# 3_-MCU.net
KiCad netlist of a schematic drawn in Altium Designer
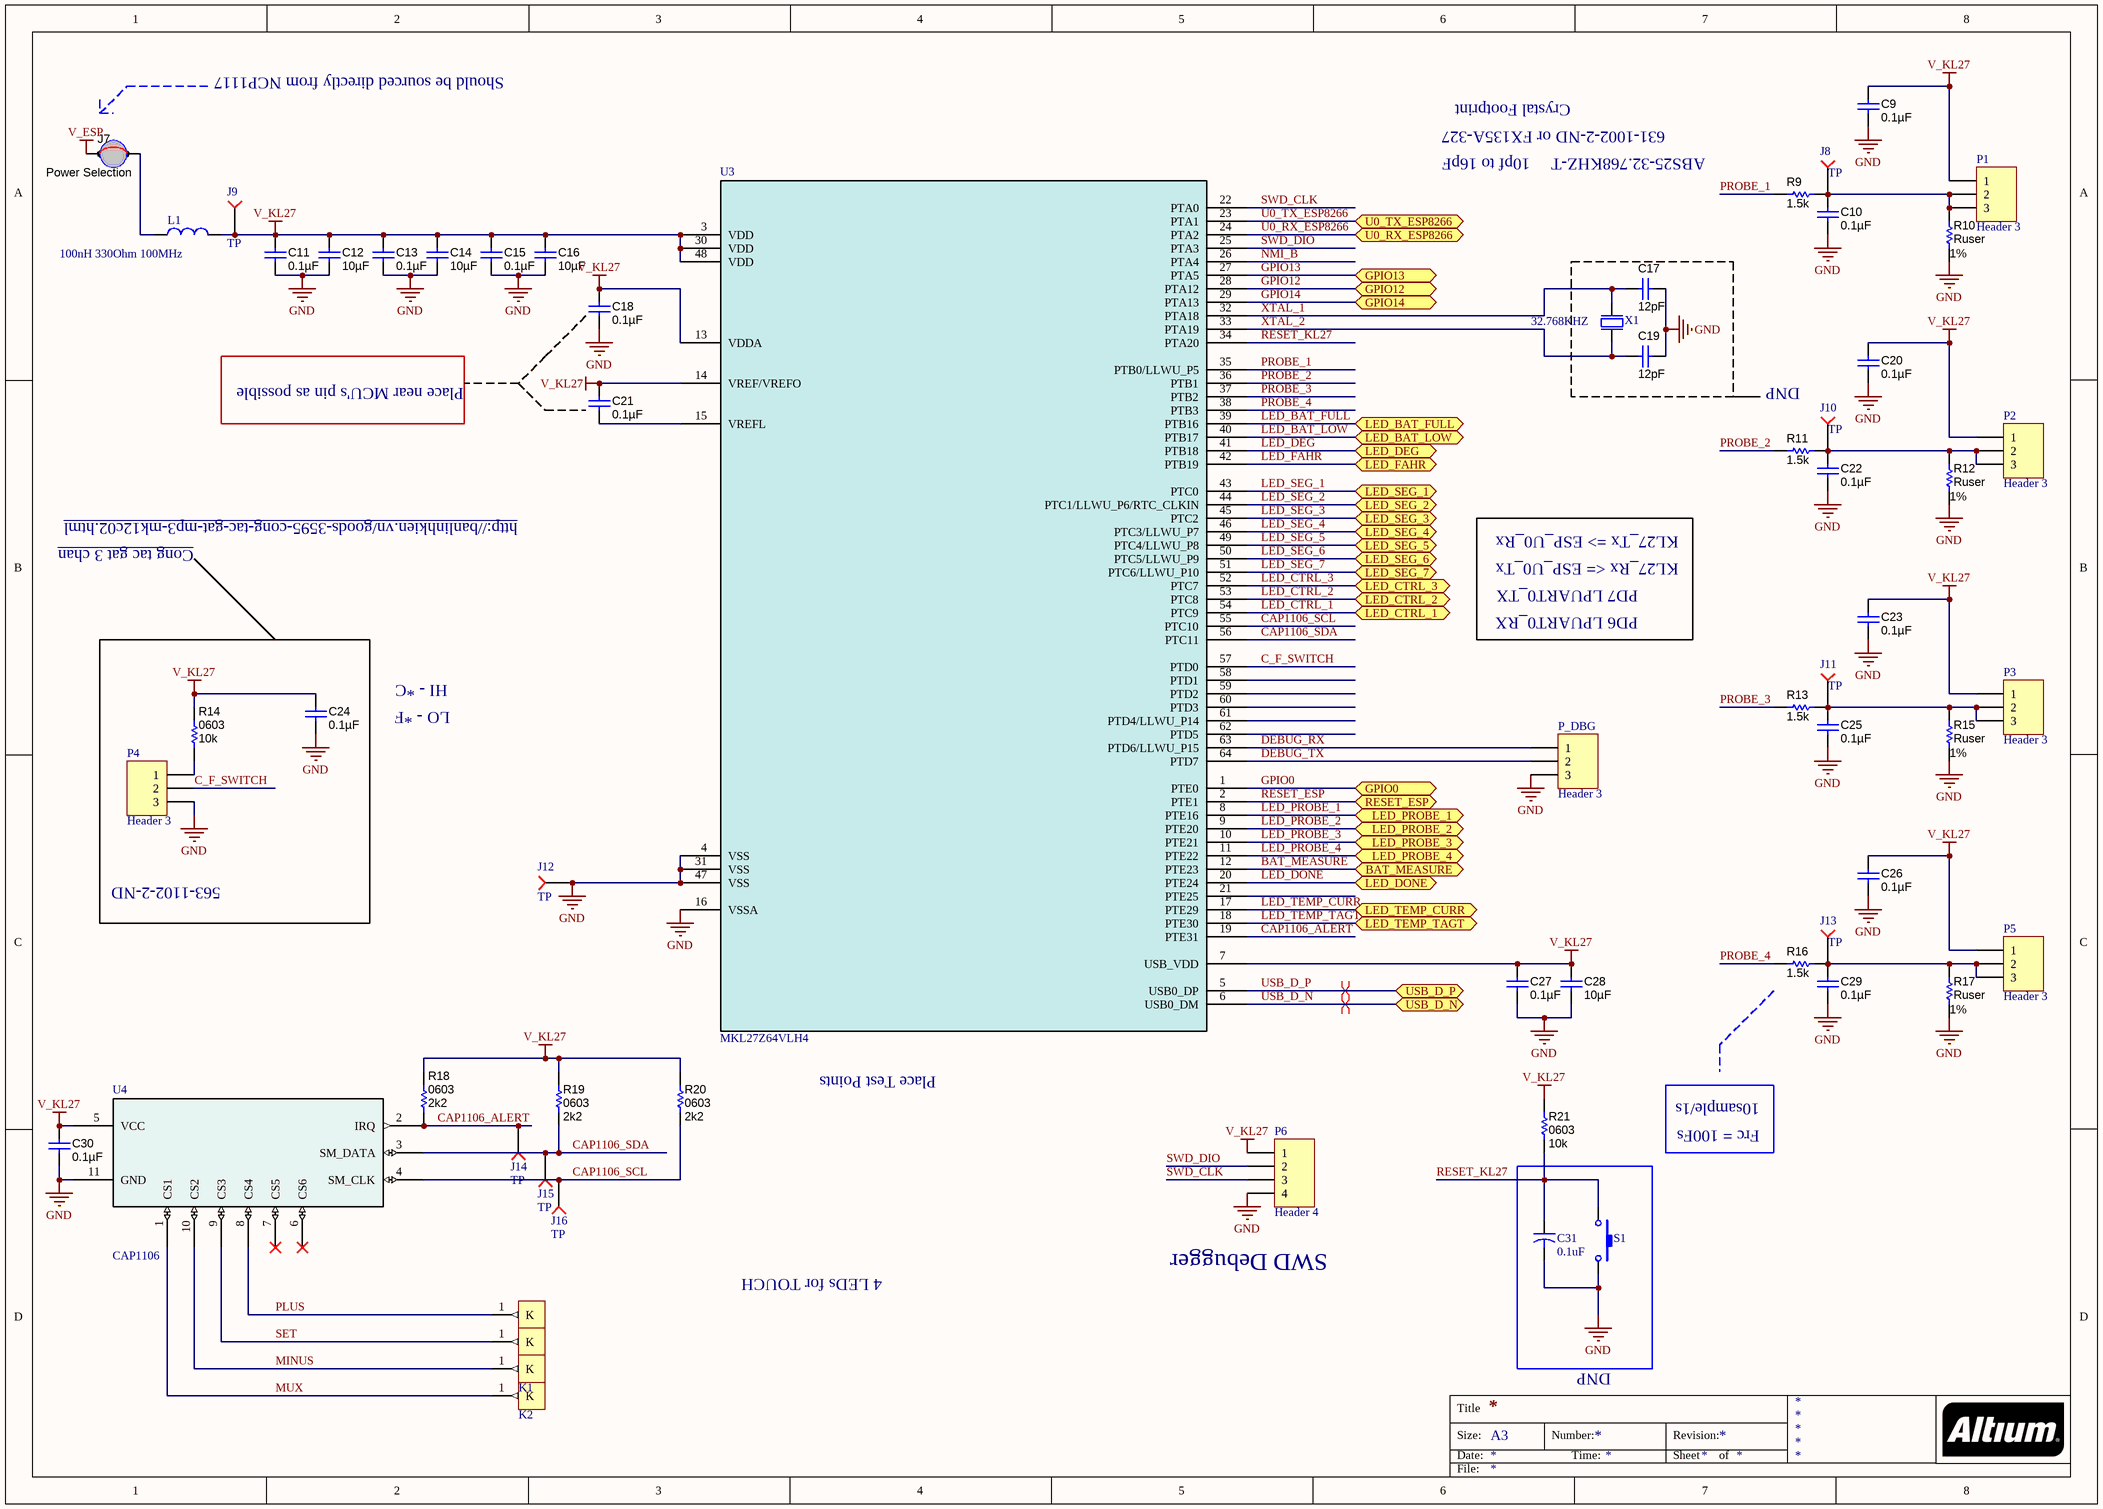
[diagram p0: [3]-MCU.SchDoc]

(export (version "E")
  (design (tool "Eeschema 10.0.6"))
  (components
    (comp (ref "C9")
      (value "0603YC104JAT2A")
      (footprint "0603")
      (description "CAP, CERM, 0.1uF, 16V, +/-5%, X7R, 0603")
      (fields
        (field (name "MANUFACTURER") "AVX")
        (field (name "VALUEDISPLAYED") "0.1µF")
        (field (name "PUBLISHER") "Texas Instruments")
      )
      (libsource (lib "tuongpv2") (part "Cap_0603"))
    )
    (comp (ref "C10")
      (value "0603YC104JAT2A")
      (footprint "0603")
      (description "CAP, CERM, 0.1uF, 16V, +/-5%, X7R, 0603")
      (fields
        (field (name "MANUFACTURER") "AVX")
        (field (name "VALUEDISPLAYED") "0.1µF")
        (field (name "PUBLISHER") "Texas Instruments")
      )
      (libsource (lib "tuongpv2") (part "Cap_0603"))
    )
    (comp (ref "C11")
      (value "0603YC104JAT2A")
      (footprint "0603")
      (description "CAP, CERM, 0.1uF, 16V, +/-5%, X7R, 0603")
      (fields
        (field (name "MANUFACTURER") "AVX")
        (field (name "VALUEDISPLAYED") "0.1µF")
        (field (name "PUBLISHER") "Texas Instruments")
      )
      (libsource (lib "tuongpv2") (part "Cap_0603"))
    )
    (comp (ref "C12")
      (value "0603YC104JAT2A")
      (footprint "0603")
      (description "CAP, CERM, 0.1uF, 16V, +/-5%, X7R, 0603")
      (fields
        (field (name "MANUFACTURER") "AVX")
        (field (name "VALUEDISPLAYED") "10µF")
        (field (name "PUBLISHER") "Texas Instruments")
      )
      (libsource (lib "tuongpv2") (part "Cap_0603"))
    )
    (comp (ref "C13")
      (value "0603YC104JAT2A")
      (footprint "0603")
      (description "CAP, CERM, 0.1uF, 16V, +/-5%, X7R, 0603")
      (fields
        (field (name "MANUFACTURER") "AVX")
        (field (name "VALUEDISPLAYED") "0.1µF")
        (field (name "PUBLISHER") "Texas Instruments")
      )
      (libsource (lib "tuongpv2") (part "Cap_0603"))
    )
    (comp (ref "C14")
      (value "0603YC104JAT2A")
      (footprint "0603")
      (description "CAP, CERM, 0.1uF, 16V, +/-5%, X7R, 0603")
      (fields
        (field (name "MANUFACTURER") "AVX")
        (field (name "VALUEDISPLAYED") "10µF")
        (field (name "PUBLISHER") "Texas Instruments")
      )
      (libsource (lib "tuongpv2") (part "Cap_0603"))
    )
    (comp (ref "C15")
      (value "0603YC104JAT2A")
      (footprint "0603")
      (description "CAP, CERM, 0.1uF, 16V, +/-5%, X7R, 0603")
      (fields
        (field (name "MANUFACTURER") "AVX")
        (field (name "VALUEDISPLAYED") "0.1µF")
        (field (name "PUBLISHER") "Texas Instruments")
      )
      (libsource (lib "tuongpv2") (part "Cap_0603"))
    )
    (comp (ref "C16")
      (value "0603YC104JAT2A")
      (footprint "0603")
      (description "CAP, CERM, 0.1uF, 16V, +/-5%, X7R, 0603")
      (fields
        (field (name "MANUFACTURER") "AVX")
        (field (name "VALUEDISPLAYED") "10µF")
        (field (name "PUBLISHER") "Texas Instruments")
      )
      (libsource (lib "tuongpv2") (part "Cap_0603"))
    )
    (comp (ref "C17")
      (value "0603YC104JAT2A")
      (footprint "0603")
      (description "CAP, CERM, 0.1uF, 16V, +/-5%, X7R, 0603")
      (fields
        (field (name "MANUFACTURER") "AVX")
        (field (name "VALUEDISPLAYED") "12pF")
        (field (name "PUBLISHER") "Texas Instruments")
      )
      (libsource (lib "tuongpv2") (part "Cap_0603"))
    )
    (comp (ref "C18")
      (value "0603YC104JAT2A")
      (footprint "0603")
      (description "CAP, CERM, 0.1uF, 16V, +/-5%, X7R, 0603")
      (fields
        (field (name "MANUFACTURER") "AVX")
        (field (name "VALUEDISPLAYED") "0.1µF")
        (field (name "PUBLISHER") "Texas Instruments")
      )
      (libsource (lib "tuongpv2") (part "Cap_0603"))
    )
    (comp (ref "C19")
      (value "0603YC104JAT2A")
      (footprint "0603")
      (description "CAP, CERM, 0.1uF, 16V, +/-5%, X7R, 0603")
      (fields
        (field (name "MANUFACTURER") "AVX")
        (field (name "VALUEDISPLAYED") "12pF")
        (field (name "PUBLISHER") "Texas Instruments")
      )
      (libsource (lib "tuongpv2") (part "Cap_0603"))
    )
    (comp (ref "C20")
      (value "0603YC104JAT2A")
      (footprint "0603")
      (description "CAP, CERM, 0.1uF, 16V, +/-5%, X7R, 0603")
      (fields
        (field (name "MANUFACTURER") "AVX")
        (field (name "VALUEDISPLAYED") "0.1µF")
        (field (name "PUBLISHER") "Texas Instruments")
      )
      (libsource (lib "tuongpv2") (part "Cap_0603"))
    )
    (comp (ref "C21")
      (value "0603YC104JAT2A")
      (footprint "0603")
      (description "CAP, CERM, 0.1uF, 16V, +/-5%, X7R, 0603")
      (fields
        (field (name "MANUFACTURER") "AVX")
        (field (name "VALUEDISPLAYED") "0.1µF")
        (field (name "PUBLISHER") "Texas Instruments")
      )
      (libsource (lib "tuongpv2") (part "Cap_0603"))
    )
    (comp (ref "C22")
      (value "0603YC104JAT2A")
      (footprint "0603")
      (description "CAP, CERM, 0.1uF, 16V, +/-5%, X7R, 0603")
      (fields
        (field (name "MANUFACTURER") "AVX")
        (field (name "VALUEDISPLAYED") "0.1µF")
        (field (name "PUBLISHER") "Texas Instruments")
      )
      (libsource (lib "tuongpv2") (part "Cap_0603"))
    )
    (comp (ref "C23")
      (value "0603YC104JAT2A")
      (footprint "0603")
      (description "CAP, CERM, 0.1uF, 16V, +/-5%, X7R, 0603")
      (fields
        (field (name "MANUFACTURER") "AVX")
        (field (name "VALUEDISPLAYED") "0.1µF")
        (field (name "PUBLISHER") "Texas Instruments")
      )
      (libsource (lib "tuongpv2") (part "Cap_0603"))
    )
    (comp (ref "C24")
      (value "0603YC104JAT2A")
      (footprint "0603")
      (description "CAP, CERM, 0.1uF, 16V, +/-5%, X7R, 0603")
      (fields
        (field (name "MANUFACTURER") "AVX")
        (field (name "VALUEDISPLAYED") "0.1µF")
        (field (name "PUBLISHER") "Texas Instruments")
      )
      (libsource (lib "tuongpv2") (part "Cap_0603"))
    )
    (comp (ref "C25")
      (value "0603YC104JAT2A")
      (footprint "0603")
      (description "CAP, CERM, 0.1uF, 16V, +/-5%, X7R, 0603")
      (fields
        (field (name "MANUFACTURER") "AVX")
        (field (name "VALUEDISPLAYED") "0.1µF")
        (field (name "PUBLISHER") "Texas Instruments")
      )
      (libsource (lib "tuongpv2") (part "Cap_0603"))
    )
    (comp (ref "C26")
      (value "0603YC104JAT2A")
      (footprint "0603")
      (description "CAP, CERM, 0.1uF, 16V, +/-5%, X7R, 0603")
      (fields
        (field (name "MANUFACTURER") "AVX")
        (field (name "VALUEDISPLAYED") "0.1µF")
        (field (name "PUBLISHER") "Texas Instruments")
      )
      (libsource (lib "tuongpv2") (part "Cap_0603"))
    )
    (comp (ref "C27")
      (value "0603YC104JAT2A")
      (footprint "0603")
      (description "CAP, CERM, 0.1uF, 16V, +/-5%, X7R, 0603")
      (fields
        (field (name "MANUFACTURER") "AVX")
        (field (name "VALUEDISPLAYED") "0.1µF")
        (field (name "PUBLISHER") "Texas Instruments")
      )
      (libsource (lib "tuongpv2") (part "Cap_0603"))
    )
    (comp (ref "C28")
      (value "0603YC104JAT2A")
      (footprint "0603")
      (description "CAP, CERM, 0.1uF, 16V, +/-5%, X7R, 0603")
      (fields
        (field (name "MANUFACTURER") "AVX")
        (field (name "VALUEDISPLAYED") "10µF")
        (field (name "PUBLISHER") "Texas Instruments")
      )
      (libsource (lib "tuongpv2") (part "Cap_0603"))
    )
    (comp (ref "C29")
      (value "0603YC104JAT2A")
      (footprint "0603")
      (description "CAP, CERM, 0.1uF, 16V, +/-5%, X7R, 0603")
      (fields
        (field (name "MANUFACTURER") "AVX")
        (field (name "VALUEDISPLAYED") "0.1µF")
        (field (name "PUBLISHER") "Texas Instruments")
      )
      (libsource (lib "tuongpv2") (part "Cap_0603"))
    )
    (comp (ref "C30")
      (value "0603YC104JAT2A")
      (footprint "0603")
      (description "CAP, CERM, 0.1uF, 16V, +/-5%, X7R, 0603")
      (fields
        (field (name "MANUFACTURER") "AVX")
        (field (name "VALUEDISPLAYED") "0.1µF")
        (field (name "PUBLISHER") "Texas Instruments")
      )
      (libsource (lib "tuongpv2") (part "Cap_0603"))
    )
    (comp (ref "C31")
      (value "0.1uF")
      (footprint "0603")
      (description "Ceramic")
      (fields (field (name "PUBLISHER") "Altium Limited"))
      (libsource (lib "Capacitor") (part "Cap 0805"))
    )
    (comp (ref "J7")
      (value "Power Selection")
      (footprint "HDR1X2")
      (description "Jumper Wire, 200mil spacing, Red, pkg of 200")
      (fields
        (field (name "PARTNUMBER") "923345-02-C")
        (field (name "MANUFACTURER") "3M")
        (field (name "SYMBOLCREATOR") "a0412235")
        (field (name "PUBLISHER") "Texas Instruments")
      )
      (libsource (lib "Connectors") (part "923345-02-C"))
    )
    (comp (ref "J8")
      (value "TP")
      (footprint "TP")
      (description "Test point (true)")
      (libsource (lib "Cty1") (part "TP"))
    )
    (comp (ref "J9")
      (value "TP")
      (footprint "TP")
      (description "Test point (true)")
      (libsource (lib "Cty1") (part "TP"))
    )
    (comp (ref "J10")
      (value "TP")
      (footprint "TP")
      (description "Test point (true)")
      (libsource (lib "Cty1") (part "TP"))
    )
    (comp (ref "J11")
      (value "TP")
      (footprint "TP")
      (description "Test point (true)")
      (libsource (lib "Cty1") (part "TP"))
    )
    (comp (ref "J12")
      (value "TP")
      (footprint "TP")
      (description "Test point (true)")
      (libsource (lib "Cty1") (part "TP"))
    )
    (comp (ref "J13")
      (value "TP")
      (footprint "TP")
      (description "Test point (true)")
      (libsource (lib "Cty1") (part "TP"))
    )
    (comp (ref "J14")
      (value "TP")
      (footprint "TP")
      (description "Test point (true)")
      (libsource (lib "Cty1") (part "TP"))
    )
    (comp (ref "J15")
      (value "TP")
      (footprint "TP")
      (description "Test point (true)")
      (libsource (lib "Cty1") (part "TP"))
    )
    (comp (ref "J16")
      (value "TP")
      (footprint "TP")
      (description "Test point (true)")
      (libsource (lib "Cty1") (part "TP"))
    )
    (comp (ref "K1")
      (value "Single_Key")
      (footprint "PAD_FINGETIP")
      (description "Single Key Touch")
      (fields (field (name "CREATED BY") "TuongPV"))
      (libsource (lib "TouchLib") (part "Single_Key"))
    )
    (comp (ref "K2")
      (value "Single_Key")
      (footprint "PAD_FINGETIP")
      (description "Single Key Touch")
      (fields (field (name "CREATED BY") "TuongPV"))
      (libsource (lib "TouchLib") (part "Single_Key"))
    )
    (comp (ref "K3")
      (value "Single_Key")
      (footprint "PAD_FINGETIP")
      (description "Single Key Touch")
      (fields (field (name "CREATED BY") "TuongPV"))
      (libsource (lib "TouchLib") (part "Single_Key"))
    )
    (comp (ref "K4")
      (value "Single_Key")
      (footprint "PAD_FINGETIP")
      (description "Single Key Touch")
      (fields (field (name "CREATED BY") "TuongPV"))
      (libsource (lib "TouchLib") (part "Single_Key"))
    )
    (comp (ref "L1")
      (value "100nH 330Ohm 100MHz")
      (footprint "0805")
      (description "Inductor")
      (libsource (lib "TuongLib") (part "L1"))
    )
    (comp (ref "P1")
      (value "Header 3")
      (footprint "JACK_MONO")
      (description "Header, 3-Pin")
      (fields (field (name "PUBLISHER") "Altium Limited"))
      (libsource (lib "Connecter") (part "Header 3"))
    )
    (comp (ref "P2")
      (value "Header 3")
      (footprint "JACK_MONO")
      (description "Header, 3-Pin")
      (fields (field (name "PUBLISHER") "Altium Limited"))
      (libsource (lib "Connecter") (part "Header 3"))
    )
    (comp (ref "P3")
      (value "Header 3")
      (footprint "JACK_MONO")
      (description "Header, 3-Pin")
      (fields (field (name "PUBLISHER") "Altium Limited"))
      (libsource (lib "Connecter") (part "Header 3"))
    )
    (comp (ref "P4")
      (value "Header 3")
      (footprint "SW_Slide")
      (description "Header, 3-Pin")
      (fields (field (name "PUBLISHER") "Altium Limited"))
      (libsource (lib "") (part "Header 3_1"))
    )
    (comp (ref "P5")
      (value "Header 3")
      (footprint "JACK_MONO")
      (description "Header, 3-Pin")
      (fields (field (name "PUBLISHER") "Altium Limited"))
      (libsource (lib "Connecter") (part "Header 3"))
    )
    (comp (ref "P6")
      (value "Header 4")
      (footprint "hdR1x4")
      (description "Header, 4-Pin")
      (fields (field (name "PUBLISHER") "Altium Limited"))
      (libsource (lib "Connecter") (part "Header 4"))
    )
    (comp (ref "P_DBG")
      (value "Header 3")
      (footprint "HDR1X3")
      (description "Header, 3-Pin")
      (fields (field (name "PUBLISHER") "Altium Limited"))
      (libsource (lib "Connecter") (part "Header 3"))
    )
    (comp (ref "R9")
      (value "1.5k")
      (footprint "0603")
      (description "RES, 1.00k ohm, 1%, 0.1W, 0603")
      (fields
        (field (name "PARTNUMBER") "CRCW06031K00FKEA")
        (field (name "MANUFACTURER") "Vishay-Dale")
        (field (name "PUBLISHER") "Texas Instruments")
      )
      (libsource (lib "tuongpv2") (part "R0603"))
    )
    (comp (ref "R10")
      (value "Ruser")
      (footprint "0603")
      (description "RES, 1.00k ohm, 1%, 0.1W, 0603")
      (fields
        (field (name "PARTNUMBER") "CRCW06031K00FKEA")
        (field (name "MANUFACTURER") "Vishay-Dale")
        (field (name "VALUE1") "1%")
        (field (name "PUBLISHER") "Texas Instruments")
      )
      (libsource (lib "tuongpv2") (part "R0603"))
    )
    (comp (ref "R11")
      (value "1.5k")
      (footprint "0603")
      (description "RES, 1.00k ohm, 1%, 0.1W, 0603")
      (fields
        (field (name "PARTNUMBER") "CRCW06031K00FKEA")
        (field (name "MANUFACTURER") "Vishay-Dale")
        (field (name "PUBLISHER") "Texas Instruments")
      )
      (libsource (lib "tuongpv2") (part "R0603"))
    )
    (comp (ref "R12")
      (value "Ruser")
      (footprint "0603")
      (description "RES, 1.00k ohm, 1%, 0.1W, 0603")
      (fields
        (field (name "PARTNUMBER") "CRCW06031K00FKEA")
        (field (name "MANUFACTURER") "Vishay-Dale")
        (field (name "VALUE1") "1%")
        (field (name "PUBLISHER") "Texas Instruments")
      )
      (libsource (lib "tuongpv2") (part "R0603"))
    )
    (comp (ref "R13")
      (value "1.5k")
      (footprint "0603")
      (description "RES, 1.00k ohm, 1%, 0.1W, 0603")
      (fields
        (field (name "PARTNUMBER") "CRCW06031K00FKEA")
        (field (name "MANUFACTURER") "Vishay-Dale")
        (field (name "PUBLISHER") "Texas Instruments")
      )
      (libsource (lib "tuongpv2") (part "R0603"))
    )
    (comp (ref "R14")
      (value "10k")
      (footprint "0603")
      (description "RES 5%, 0.125W, 0805")
      (fields
        (field (name "PARTNUMBER") "CRCW08051K00JNEA")
        (field (name "MANUFACTURER") "Vishay-Dale")
        (field (name "VALUE1") "0603")
        (field (name "PUBLISHER") "Texas Instruments")
      )
      (libsource (lib "Cty1") (part "R0805_025W"))
    )
    (comp (ref "R15")
      (value "Ruser")
      (footprint "0603")
      (description "RES, 1.00k ohm, 1%, 0.1W, 0603")
      (fields
        (field (name "PARTNUMBER") "CRCW06031K00FKEA")
        (field (name "MANUFACTURER") "Vishay-Dale")
        (field (name "VALUE1") "1%")
        (field (name "PUBLISHER") "Texas Instruments")
      )
      (libsource (lib "tuongpv2") (part "R0603"))
    )
    (comp (ref "R16")
      (value "1.5k")
      (footprint "0603")
      (description "RES, 1.00k ohm, 1%, 0.1W, 0603")
      (fields
        (field (name "PARTNUMBER") "CRCW06031K00FKEA")
        (field (name "MANUFACTURER") "Vishay-Dale")
        (field (name "PUBLISHER") "Texas Instruments")
      )
      (libsource (lib "tuongpv2") (part "R0603"))
    )
    (comp (ref "R17")
      (value "Ruser")
      (footprint "0603")
      (description "RES, 1.00k ohm, 1%, 0.1W, 0603")
      (fields
        (field (name "PARTNUMBER") "CRCW06031K00FKEA")
        (field (name "MANUFACTURER") "Vishay-Dale")
        (field (name "VALUE1") "1%")
        (field (name "PUBLISHER") "Texas Instruments")
      )
      (libsource (lib "tuongpv2") (part "R0603"))
    )
    (comp (ref "R18")
      (value "2k2")
      (footprint "0603")
      (description "RES 5%, 0.125W, 0805")
      (fields
        (field (name "PARTNUMBER") "CRCW08051K00JNEA")
        (field (name "MANUFACTURER") "Vishay-Dale")
        (field (name "VALUE1") "0603")
        (field (name "PUBLISHER") "Texas Instruments")
      )
      (libsource (lib "Cty1") (part "R0805_025W"))
    )
    (comp (ref "R19")
      (value "2k2")
      (footprint "0603")
      (description "RES 5%, 0.125W, 0805")
      (fields
        (field (name "PARTNUMBER") "CRCW08051K00JNEA")
        (field (name "MANUFACTURER") "Vishay-Dale")
        (field (name "VALUE1") "0603")
        (field (name "PUBLISHER") "Texas Instruments")
      )
      (libsource (lib "Cty1") (part "R0805_025W"))
    )
    (comp (ref "R20")
      (value "2k2")
      (footprint "0603")
      (description "RES 5%, 0.125W, 0805")
      (fields
        (field (name "PARTNUMBER") "CRCW08051K00JNEA")
        (field (name "MANUFACTURER") "Vishay-Dale")
        (field (name "VALUE1") "0603")
        (field (name "PUBLISHER") "Texas Instruments")
      )
      (libsource (lib "Cty1") (part "R0805_025W"))
    )
    (comp (ref "R21")
      (value "10k")
      (footprint "0603")
      (description "RES 5%, 0.125W, 0805")
      (fields
        (field (name "PARTNUMBER") "CRCW08051K00JNEA")
        (field (name "MANUFACTURER") "Vishay-Dale")
        (field (name "VALUE1") "0603")
        (field (name "PUBLISHER") "Texas Instruments")
      )
      (libsource (lib "Cty1") (part "R0805_025W"))
    )
    (comp (ref "S1")
      (value "SW-SMD")
      (footprint "SW-SMD")
      (description "Switch")
      (fields (field (name "PUBLISHER") "Altium Limited"))
      (libsource (lib "Cty1") (part "SW-SMD"))
    )
    (comp (ref "U3")
      (value "MKL27Z64VLH4")
      (footprint "98ASS23234W")
      (description "ARM cortex M0+ 64Kb Flash LQFP-64")
      (fields (field (name "MANUFACTURER_PART_NUMBER") "mkl27z64vlh4"))
      (libsource (lib "uC") (part "MKL27Z64VLH4"))
    )
    (comp (ref "U4")
      (value "CAP1106")
      (footprint "TDFN33-10pin")
      (description "6 Channel Capacitive Touch Sensor")
      (fields (field (name "MANUFACTURER") "Microchip"))
      (libsource (lib "SMPS_IC") (part "CAP1106"))
    )
    (comp (ref "X1")
      (value "32.768KHZ")
      (footprint "XTAL_3215")
      (description "XTAL SMD 3215, 32.768kHz, 9pF, ±20ppm")
      (fields
        (field (name "PART NUMBER") "XTAL_FC-135 32.768k")
        (field (name "MANUFACTURER") "Epson Toyocom")
        (field (name "PUBLISHER") "Nordic Semiconductor")
      )
      (libsource (lib "Cty1") (part "XTAL_SMD3215"))
    )
  )
  (nets
    (net (code "1") (name "/BAT_MEASURE") (class "Default")
      (node (ref "U3") (pin "12") (pinfunction "PTE23_12") (pintype "passive"))
    )
    (net (code "2") (name "/CAP1106_ALERT") (class "Default")
      (node (ref "J14") (pin "0") (pinfunction "0_0") (pintype "passive"))
      (node (ref "R18") (pin "2") (pinfunction "2_2") (pintype "passive"))
      (node (ref "U3") (pin "19") (pinfunction "PTE31_19") (pintype "passive"))
      (node (ref "U4") (pin "2") (pinfunction "IRQ_2") (pintype "output"))
    )
    (net (code "3") (name "/CAP1106_SCL") (class "Default")
      (node (ref "J16") (pin "0") (pinfunction "0_0") (pintype "passive"))
      (node (ref "R20") (pin "2") (pinfunction "2_2") (pintype "passive"))
      (node (ref "U3") (pin "55") (pinfunction "PTC10_55") (pintype "passive"))
      (node (ref "U4") (pin "4") (pinfunction "SM_CLK_4") (pintype "bidirectional"))
    )
    (net (code "4") (name "/CAP1106_SDA") (class "Default")
      (node (ref "J15") (pin "0") (pinfunction "0_0") (pintype "passive"))
      (node (ref "R19") (pin "2") (pinfunction "2_2") (pintype "passive"))
      (node (ref "U3") (pin "56") (pinfunction "PTC11_56") (pintype "passive"))
      (node (ref "U4") (pin "3") (pinfunction "SM_DATA_3") (pintype "bidirectional"))
    )
    (net (code "5") (name "/C_F_SWITCH") (class "Default")
      (node (ref "P4") (pin "2") (pinfunction "2_2") (pintype "passive"))
      (node (ref "U3") (pin "57") (pinfunction "PTD0_57") (pintype "passive"))
    )
    (net (code "6") (name "/DEBUG_RX") (class "Default")
      (node (ref "P_DBG") (pin "1") (pinfunction "1_1") (pintype "passive"))
      (node (ref "U3") (pin "63") (pinfunction "PTD6/LLWU_P15_63") (pintype "passive"))
    )
    (net (code "7") (name "/DEBUG_TX") (class "Default")
      (node (ref "P_DBG") (pin "2") (pinfunction "2_2") (pintype "passive"))
      (node (ref "U3") (pin "64") (pinfunction "PTD7_64") (pintype "passive"))
    )
    (net (code "8") (name "/GPIO0") (class "Default")
      (node (ref "U3") (pin "1") (pinfunction "PTE0_1") (pintype "passive"))
    )
    (net (code "9") (name "/GPIO12") (class "Default")
      (node (ref "U3") (pin "28") (pinfunction "PTA12_28") (pintype "passive"))
    )
    (net (code "10") (name "/GPIO13") (class "Default")
      (node (ref "U3") (pin "27") (pinfunction "PTA5_27") (pintype "passive"))
    )
    (net (code "11") (name "/GPIO14") (class "Default")
      (node (ref "U3") (pin "29") (pinfunction "PTA13_29") (pintype "passive"))
    )
    (net (code "12") (name "/LED_BAT_FULL") (class "Default")
      (node (ref "U3") (pin "39") (pinfunction "PTB16_39") (pintype "passive"))
    )
    (net (code "13") (name "/LED_BAT_LOW") (class "Default")
      (node (ref "U3") (pin "40") (pinfunction "PTB17_40") (pintype "passive"))
    )
    (net (code "14") (name "/LED_CTRL_1") (class "Default")
      (node (ref "U3") (pin "54") (pinfunction "PTC9_54") (pintype "passive"))
    )
    (net (code "15") (name "/LED_CTRL_2") (class "Default")
      (node (ref "U3") (pin "53") (pinfunction "PTC8_53") (pintype "passive"))
    )
    (net (code "16") (name "/LED_CTRL_3") (class "Default")
      (node (ref "U3") (pin "52") (pinfunction "PTC7_52") (pintype "passive"))
    )
    (net (code "17") (name "/LED_DEG") (class "Default")
      (node (ref "U3") (pin "41") (pinfunction "PTB18_41") (pintype "passive"))
    )
    (net (code "18") (name "/LED_DONE") (class "Default")
      (node (ref "U3") (pin "20") (pinfunction "PTE24_20") (pintype "passive"))
    )
    (net (code "19") (name "/LED_FAHR") (class "Default")
      (node (ref "U3") (pin "42") (pinfunction "PTB19_42") (pintype "passive"))
    )
    (net (code "20") (name "/LED_PROBE_1") (class "Default")
      (node (ref "U3") (pin "8") (pinfunction "PTE16_8") (pintype "passive"))
    )
    (net (code "21") (name "/LED_PROBE_2") (class "Default")
      (node (ref "U3") (pin "9") (pinfunction "PTE20_9") (pintype "passive"))
    )
    (net (code "22") (name "/LED_PROBE_3") (class "Default")
      (node (ref "U3") (pin "10") (pinfunction "PTE21_10") (pintype "passive"))
    )
    (net (code "23") (name "/LED_PROBE_4") (class "Default")
      (node (ref "U3") (pin "11") (pinfunction "PTE22_11") (pintype "passive"))
    )
    (net (code "24") (name "/LED_SEG_1") (class "Default")
      (node (ref "U3") (pin "43") (pinfunction "PTC0_43") (pintype "passive"))
    )
    (net (code "25") (name "/LED_SEG_2") (class "Default")
      (node (ref "U3") (pin "44") (pinfunction "PTC1/LLWU_P6/RTC_CLKIN_44") (pintype "passive"))
    )
    (net (code "26") (name "/LED_SEG_3") (class "Default")
      (node (ref "U3") (pin "45") (pinfunction "PTC2_45") (pintype "passive"))
    )
    (net (code "27") (name "/LED_SEG_4") (class "Default")
      (node (ref "U3") (pin "46") (pinfunction "PTC3/LLWU_P7_46") (pintype "passive"))
    )
    (net (code "28") (name "/LED_SEG_5") (class "Default")
      (node (ref "U3") (pin "49") (pinfunction "PTC4/LLWU_P8_49") (pintype "passive"))
    )
    (net (code "29") (name "/LED_SEG_6") (class "Default")
      (node (ref "U3") (pin "50") (pinfunction "PTC5/LLWU_P9_50") (pintype "passive"))
    )
    (net (code "30") (name "/LED_SEG_7") (class "Default")
      (node (ref "U3") (pin "51") (pinfunction "PTC6/LLWU_P10_51") (pintype "passive"))
    )
    (net (code "31") (name "/LED_TEMP_CURR") (class "Default")
      (node (ref "U3") (pin "17") (pinfunction "PTE29_17") (pintype "passive"))
    )
    (net (code "32") (name "/LED_TEMP_TAGT") (class "Default")
      (node (ref "U3") (pin "18") (pinfunction "PTE30_18") (pintype "passive"))
    )
    (net (code "33") (name "/MINUS") (class "Default")
      (node (ref "K1") (pin "1") (pinfunction "K_1") (pintype "output"))
      (node (ref "U4") (pin "10") (pinfunction "CS2_10") (pintype "bidirectional"))
    )
    (net (code "34") (name "/MUX") (class "Default")
      (node (ref "K2") (pin "1") (pinfunction "K_1") (pintype "output"))
      (node (ref "U4") (pin "1") (pinfunction "CS1_1") (pintype "bidirectional"))
    )
    (net (code "35") (name "/NMI_B") (class "Default")
      (node (ref "U3") (pin "26") (pinfunction "PTA4_26") (pintype "passive"))
    )
    (net (code "36") (name "/PLUS") (class "Default")
      (node (ref "K4") (pin "1") (pinfunction "K_1") (pintype "output"))
      (node (ref "U4") (pin "8") (pinfunction "CS4_8") (pintype "bidirectional"))
    )
    (net (code "37") (name "/PROBE_1") (class "Default")
      (node (ref "R9") (pin "2") (pinfunction "2_2") (pintype "passive"))
      (node (ref "U3") (pin "35") (pinfunction "PTB0/LLWU_P5_35") (pintype "passive"))
    )
    (net (code "38") (name "/PROBE_2") (class "Default")
      (node (ref "R11") (pin "2") (pinfunction "2_2") (pintype "passive"))
      (node (ref "U3") (pin "36") (pinfunction "PTB1_36") (pintype "passive"))
    )
    (net (code "39") (name "/PROBE_3") (class "Default")
      (node (ref "R13") (pin "2") (pinfunction "2_2") (pintype "passive"))
      (node (ref "U3") (pin "37") (pinfunction "PTB2_37") (pintype "passive"))
    )
    (net (code "40") (name "/PROBE_4") (class "Default")
      (node (ref "R16") (pin "2") (pinfunction "2_2") (pintype "passive"))
      (node (ref "U3") (pin "38") (pinfunction "PTB3_38") (pintype "passive"))
    )
    (net (code "41") (name "/RESET_ESP") (class "Default")
      (node (ref "U3") (pin "2") (pinfunction "PTE1_2") (pintype "passive"))
    )
    (net (code "42") (name "/RESET_KL27") (class "Default")
      (node (ref "C31") (pin "1") (pinfunction "1_1") (pintype "passive"))
      (node (ref "R21") (pin "2") (pinfunction "2_2") (pintype "passive"))
      (node (ref "S1") (pin "1") (pinfunction "1_1") (pintype "passive"))
      (node (ref "U3") (pin "34") (pinfunction "PTA20_34") (pintype "passive"))
    )
    (net (code "43") (name "/SET") (class "Default")
      (node (ref "K3") (pin "1") (pinfunction "K_1") (pintype "output"))
      (node (ref "U4") (pin "9") (pinfunction "CS3_9") (pintype "bidirectional"))
    )
    (net (code "44") (name "/SWD_CLK") (class "Default")
      (node (ref "P6") (pin "3") (pinfunction "3_3") (pintype "passive"))
      (node (ref "U3") (pin "22") (pinfunction "PTA0_22") (pintype "passive"))
    )
    (net (code "45") (name "/SWD_DIO") (class "Default")
      (node (ref "P6") (pin "2") (pinfunction "2_2") (pintype "passive"))
      (node (ref "U3") (pin "25") (pinfunction "PTA3_25") (pintype "passive"))
    )
    (net (code "46") (name "/U0_RX_ESP8266") (class "Default")
      (node (ref "U3") (pin "24") (pinfunction "PTA2_24") (pintype "passive"))
    )
    (net (code "47") (name "/U0_TX_ESP8266") (class "Default")
      (node (ref "U3") (pin "23") (pinfunction "PTA1_23") (pintype "passive"))
    )
    (net (code "48") (name "/USB_D_N") (class "Default")
      (node (ref "U3") (pin "6") (pinfunction "USB0_DM_6") (pintype "passive"))
    )
    (net (code "49") (name "/USB_D_P") (class "Default")
      (node (ref "U3") (pin "5") (pinfunction "USB0_DP_5") (pintype "passive"))
    )
    (net (code "50") (name "/XTAL_1") (class "Default")
      (node (ref "C17") (pin "1") (pinfunction "1_1") (pintype "passive"))
      (node (ref "U3") (pin "32") (pinfunction "PTA18_32") (pintype "passive"))
      (node (ref "X1") (pin "2") (pinfunction "out_2") (pintype "passive"))
    )
    (net (code "51") (name "/XTAL_2") (class "Default")
      (node (ref "C19") (pin "1") (pinfunction "1_1") (pintype "passive"))
      (node (ref "U3") (pin "33") (pinfunction "PTA19_33") (pintype "passive"))
      (node (ref "X1") (pin "1") (pinfunction "inp_1") (pintype "passive"))
    )
    (net (code "52") (name "GND") (class "Default")
      (node (ref "C10") (pin "2") (pinfunction "2_2") (pintype "passive"))
      (node (ref "C11") (pin "2") (pinfunction "2_2") (pintype "passive"))
      (node (ref "C12") (pin "2") (pinfunction "2_2") (pintype "passive"))
      (node (ref "C13") (pin "2") (pinfunction "2_2") (pintype "passive"))
      (node (ref "C14") (pin "2") (pinfunction "2_2") (pintype "passive"))
      (node (ref "C15") (pin "2") (pinfunction "2_2") (pintype "passive"))
      (node (ref "C16") (pin "2") (pinfunction "2_2") (pintype "passive"))
      (node (ref "C17") (pin "2") (pinfunction "2_2") (pintype "passive"))
      (node (ref "C18") (pin "2") (pinfunction "2_2") (pintype "passive"))
      (node (ref "C19") (pin "2") (pinfunction "2_2") (pintype "passive"))
      (node (ref "C20") (pin "2") (pinfunction "2_2") (pintype "passive"))
      (node (ref "C22") (pin "2") (pinfunction "2_2") (pintype "passive"))
      (node (ref "C23") (pin "2") (pinfunction "2_2") (pintype "passive"))
      (node (ref "C24") (pin "2") (pinfunction "2_2") (pintype "passive"))
      (node (ref "C25") (pin "2") (pinfunction "2_2") (pintype "passive"))
      (node (ref "C26") (pin "2") (pinfunction "2_2") (pintype "passive"))
      (node (ref "C27") (pin "2") (pinfunction "2_2") (pintype "passive"))
      (node (ref "C28") (pin "2") (pinfunction "2_2") (pintype "passive"))
      (node (ref "C29") (pin "2") (pinfunction "2_2") (pintype "passive"))
      (node (ref "C30") (pin "2") (pinfunction "2_2") (pintype "passive"))
      (node (ref "C31") (pin "2") (pinfunction "2_2") (pintype "passive"))
      (node (ref "C9") (pin "2") (pinfunction "2_2") (pintype "passive"))
      (node (ref "J12") (pin "0") (pinfunction "0_0") (pintype "passive"))
      (node (ref "P4") (pin "3") (pinfunction "3_3") (pintype "passive"))
      (node (ref "P6") (pin "4") (pinfunction "4_4") (pintype "passive"))
      (node (ref "P_DBG") (pin "3") (pinfunction "3_3") (pintype "passive"))
      (node (ref "R10") (pin "1") (pinfunction "1_1") (pintype "passive"))
      (node (ref "R12") (pin "1") (pinfunction "1_1") (pintype "passive"))
      (node (ref "R15") (pin "1") (pinfunction "1_1") (pintype "passive"))
      (node (ref "R17") (pin "1") (pinfunction "1_1") (pintype "passive"))
      (node (ref "S1") (pin "2") (pinfunction "2_2") (pintype "passive"))
      (node (ref "U3") (pin "16") (pinfunction "VSSA_16") (pintype "power_in"))
      (node (ref "U3") (pin "31") (pinfunction "VSS_31") (pintype "power_in"))
      (node (ref "U3") (pin "4") (pinfunction "VSS_4") (pintype "power_in"))
      (node (ref "U3") (pin "47") (pinfunction "VSS_47") (pintype "power_in"))
      (node (ref "U4") (pin "11") (pinfunction "GND_11") (pintype "power_in"))
    )
    (net (code "53") (name "Net-(C10-Pad1)") (class "Default")
      (node (ref "C10") (pin "1") (pinfunction "1_1") (pintype "passive"))
      (node (ref "J8") (pin "0") (pinfunction "0_0") (pintype "passive"))
      (node (ref "P1") (pin "2") (pinfunction "2_2") (pintype "passive"))
      (node (ref "P1") (pin "3") (pinfunction "3_3") (pintype "passive"))
      (node (ref "R10") (pin "2") (pinfunction "2_2") (pintype "passive"))
      (node (ref "R9") (pin "1") (pinfunction "1_1") (pintype "passive"))
    )
    (net (code "54") (name "Net-(C22-Pad1)") (class "Default")
      (node (ref "C22") (pin "1") (pinfunction "1_1") (pintype "passive"))
      (node (ref "J10") (pin "0") (pinfunction "0_0") (pintype "passive"))
      (node (ref "P2") (pin "2") (pinfunction "2_2") (pintype "passive"))
      (node (ref "P2") (pin "3") (pinfunction "3_3") (pintype "passive"))
      (node (ref "R11") (pin "1") (pinfunction "1_1") (pintype "passive"))
      (node (ref "R12") (pin "2") (pinfunction "2_2") (pintype "passive"))
    )
    (net (code "55") (name "Net-(C25-Pad1)") (class "Default")
      (node (ref "C25") (pin "1") (pinfunction "1_1") (pintype "passive"))
      (node (ref "J11") (pin "0") (pinfunction "0_0") (pintype "passive"))
      (node (ref "P3") (pin "2") (pinfunction "2_2") (pintype "passive"))
      (node (ref "P3") (pin "3") (pinfunction "3_3") (pintype "passive"))
      (node (ref "R13") (pin "1") (pinfunction "1_1") (pintype "passive"))
      (node (ref "R15") (pin "2") (pinfunction "2_2") (pintype "passive"))
    )
    (net (code "56") (name "Net-(C29-Pad1)") (class "Default")
      (node (ref "C29") (pin "1") (pinfunction "1_1") (pintype "passive"))
      (node (ref "J13") (pin "0") (pinfunction "0_0") (pintype "passive"))
      (node (ref "P5") (pin "2") (pinfunction "2_2") (pintype "passive"))
      (node (ref "P5") (pin "3") (pinfunction "3_3") (pintype "passive"))
      (node (ref "R16") (pin "1") (pinfunction "1_1") (pintype "passive"))
      (node (ref "R17") (pin "2") (pinfunction "2_2") (pintype "passive"))
    )
    (net (code "57") (name "Net-(J7-Pad2)") (class "Default")
      (node (ref "J7") (pin "2") (pinfunction "2_2") (pintype "passive"))
      (node (ref "L1") (pin "1") (pinfunction "1_1") (pintype "passive"))
    )
    (net (code "58") (name "Net-(P4-Pad1)") (class "Default")
      (node (ref "P4") (pin "1") (pinfunction "1_1") (pintype "passive"))
      (node (ref "R14") (pin "2") (pinfunction "2_2") (pintype "passive"))
    )
    (net (code "59") (name "Net-(U3-VREFL)") (class "Default")
      (node (ref "C21") (pin "2") (pinfunction "2_2") (pintype "passive"))
      (node (ref "U3") (pin "15") (pinfunction "VREFL_15") (pintype "power_in"))
    )
    (net (code "60") (name "V_ESP") (class "Default")
      (node (ref "J7") (pin "1") (pinfunction "1_1") (pintype "passive"))
    )
    (net (code "61") (name "V_KL27") (class "Default")
      (node (ref "C11") (pin "1") (pinfunction "1_1") (pintype "passive"))
      (node (ref "C12") (pin "1") (pinfunction "1_1") (pintype "passive"))
      (node (ref "C13") (pin "1") (pinfunction "1_1") (pintype "passive"))
      (node (ref "C14") (pin "1") (pinfunction "1_1") (pintype "passive"))
      (node (ref "C15") (pin "1") (pinfunction "1_1") (pintype "passive"))
      (node (ref "C16") (pin "1") (pinfunction "1_1") (pintype "passive"))
      (node (ref "C18") (pin "1") (pinfunction "1_1") (pintype "passive"))
      (node (ref "C20") (pin "1") (pinfunction "1_1") (pintype "passive"))
      (node (ref "C21") (pin "1") (pinfunction "1_1") (pintype "passive"))
      (node (ref "C23") (pin "1") (pinfunction "1_1") (pintype "passive"))
      (node (ref "C24") (pin "1") (pinfunction "1_1") (pintype "passive"))
      (node (ref "C26") (pin "1") (pinfunction "1_1") (pintype "passive"))
      (node (ref "C27") (pin "1") (pinfunction "1_1") (pintype "passive"))
      (node (ref "C28") (pin "1") (pinfunction "1_1") (pintype "passive"))
      (node (ref "C30") (pin "1") (pinfunction "1_1") (pintype "passive"))
      (node (ref "C9") (pin "1") (pinfunction "1_1") (pintype "passive"))
      (node (ref "J9") (pin "0") (pinfunction "0_0") (pintype "passive"))
      (node (ref "L1") (pin "2") (pinfunction "2_2") (pintype "passive"))
      (node (ref "P1") (pin "1") (pinfunction "1_1") (pintype "passive"))
      (node (ref "P2") (pin "1") (pinfunction "1_1") (pintype "passive"))
      (node (ref "P3") (pin "1") (pinfunction "1_1") (pintype "passive"))
      (node (ref "P5") (pin "1") (pinfunction "1_1") (pintype "passive"))
      (node (ref "P6") (pin "1") (pinfunction "1_1") (pintype "passive"))
      (node (ref "R14") (pin "1") (pinfunction "1_1") (pintype "passive"))
      (node (ref "R18") (pin "1") (pinfunction "1_1") (pintype "passive"))
      (node (ref "R19") (pin "1") (pinfunction "1_1") (pintype "passive"))
      (node (ref "R20") (pin "1") (pinfunction "1_1") (pintype "passive"))
      (node (ref "R21") (pin "1") (pinfunction "1_1") (pintype "passive"))
      (node (ref "U3") (pin "13") (pinfunction "VDDA_13") (pintype "power_in"))
      (node (ref "U3") (pin "14") (pinfunction "VREF/VREFO_14") (pintype "power_in"))
      (node (ref "U3") (pin "3") (pinfunction "VDD_3") (pintype "power_in"))
      (node (ref "U3") (pin "30") (pinfunction "VDD_30") (pintype "power_in"))
      (node (ref "U3") (pin "48") (pinfunction "VDD_48") (pintype "power_in"))
      (node (ref "U3") (pin "7") (pinfunction "USB_VDD_7") (pintype "power_in"))
      (node (ref "U4") (pin "5") (pinfunction "VCC_5") (pintype "power_in"))
    )
    (net (code "62") (name "unconnected-(U3-PTD1-Pad58)") (class "Default")
      (node (ref "U3") (pin "58") (pinfunction "PTD1_58") (pintype "passive"))
    )
    (net (code "63") (name "unconnected-(U3-PTD2-Pad59)") (class "Default")
      (node (ref "U3") (pin "59") (pinfunction "PTD2_59") (pintype "passive"))
    )
    (net (code "64") (name "unconnected-(U3-PTD3-Pad60)") (class "Default")
      (node (ref "U3") (pin "60") (pinfunction "PTD3_60") (pintype "passive"))
    )
    (net (code "65") (name "unconnected-(U3-PTD4{slash}LLWU_P14-Pad61)") (class "Default")
      (node (ref "U3") (pin "61") (pinfunction "PTD4/LLWU_P14_61") (pintype "passive"))
    )
    (net (code "66") (name "unconnected-(U3-PTD5-Pad62)") (class "Default")
      (node (ref "U3") (pin "62") (pinfunction "PTD5_62") (pintype "passive"))
    )
    (net (code "67") (name "unconnected-(U3-PTE25-Pad21)") (class "Default")
      (node (ref "U3") (pin "21") (pinfunction "PTE25_21") (pintype "passive"))
    )
    (net (code "68") (name "unconnected-(U4-CS5-Pad7)") (class "Default")
      (node (ref "U4") (pin "7") (pinfunction "CS5_7") (pintype "bidirectional+no_connect"))
    )
    (net (code "69") (name "unconnected-(U4-CS6-Pad6)") (class "Default")
      (node (ref "U4") (pin "6") (pinfunction "CS6_6") (pintype "bidirectional+no_connect"))
    )
  )
)
